# DS2502_Programmer_V1_0.net
KiCad netlist of a schematic drawn in EAGLE
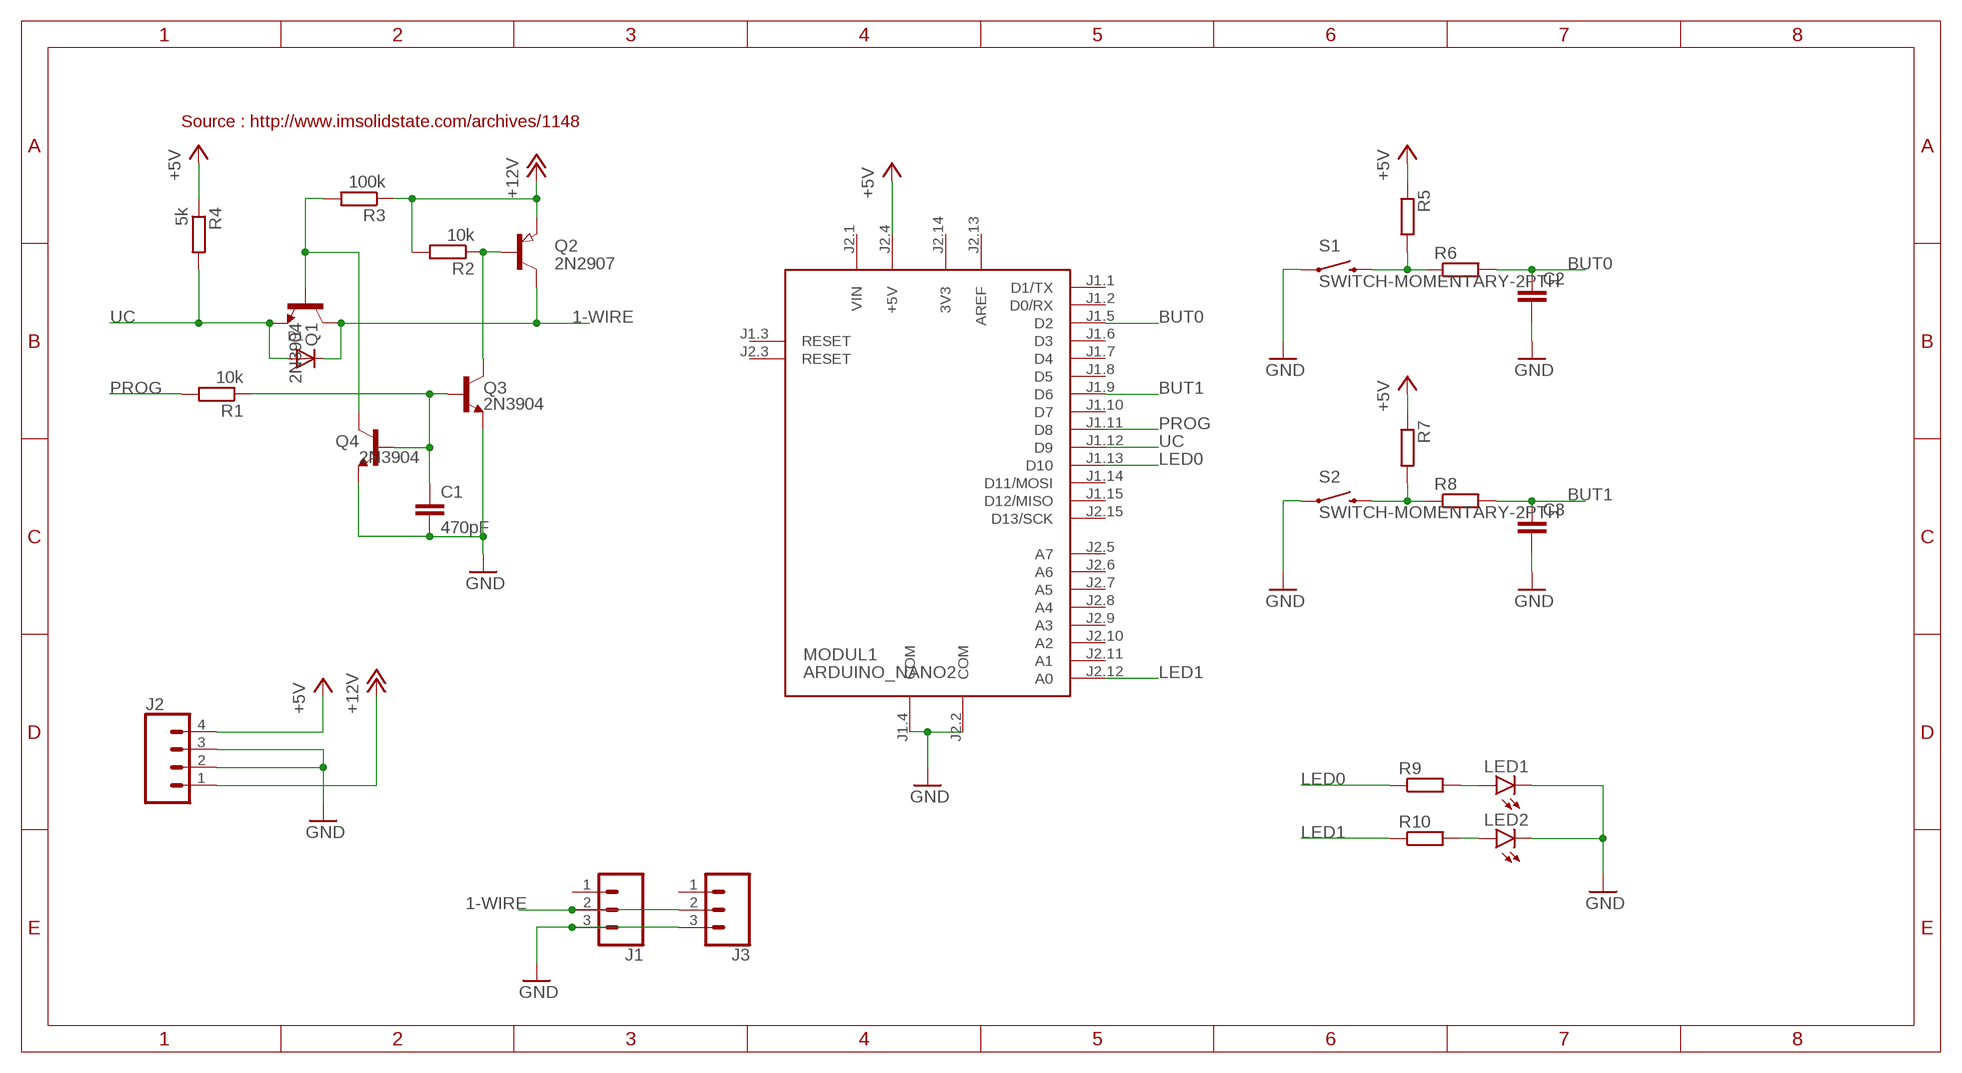
[diagram p0: schematic, sheet 1]

(export (version "E")
  (design (tool "Eeschema 10.0.6"))
  (components
    (comp (ref "C1")
      (value "470pF")
      (footprint "eagle-import:C0603")
      (libsource (lib "eagle-import") (part "C-EUC0603"))
    )
    (comp (ref "C2")
      (value "C-EUC0603")
      (footprint "eagle-import:C0603")
      (libsource (lib "eagle-import") (part "C-EUC0603"))
    )
    (comp (ref "C3")
      (value "C-EUC0603")
      (footprint "eagle-import:C0603")
      (libsource (lib "eagle-import") (part "C-EUC0603"))
    )
    (comp (ref "D1")
      (value "DIODESOD-523")
      (footprint "eagle-import:SOD-523")
      (libsource (lib "eagle-import") (part "DIODESOD-523"))
    )
    (comp (ref "J1")
      (value "CONN_03")
      (footprint "eagle-import:1X03")
      (libsource (lib "eagle-import") (part "CONN_03"))
    )
    (comp (ref "J2")
      (value "CONN_04")
      (footprint "eagle-import:1X04")
      (libsource (lib "eagle-import") (part "CONN_04"))
    )
    (comp (ref "J3")
      (value "CONN_03")
      (footprint "eagle-import:1X03")
      (libsource (lib "eagle-import") (part "CONN_03"))
    )
    (comp (ref "LED1")
      (value "LEDCHIP-LED0805")
      (footprint "eagle-import:CHIP-LED0805")
      (libsource (lib "eagle-import") (part "LEDCHIP-LED0805"))
    )
    (comp (ref "LED2")
      (value "LEDCHIP-LED0805")
      (footprint "eagle-import:CHIP-LED0805")
      (libsource (lib "eagle-import") (part "LEDCHIP-LED0805"))
    )
    (comp (ref "MODUL1")
      (value "ARDUINO_NANO2")
      (footprint "eagle-import:ARDUINO_NANO2")
      (libsource (lib "eagle-import") (part "ARDUINO_NANO2"))
    )
    (comp (ref "Q1")
      (value "2N3904")
      (footprint "eagle-import:SOT23-3")
      (libsource (lib "eagle-import") (part "TRANS_NPN-MMBTA42"))
    )
    (comp (ref "Q2")
      (value "2N2907")
      (footprint "eagle-import:SOT23")
      (libsource (lib "eagle-import") (part "PNP-TRANSISTOR_SOT23"))
    )
    (comp (ref "Q3")
      (value "2N3904")
      (footprint "eagle-import:SOT23-3")
      (libsource (lib "eagle-import") (part "TRANS_NPN-MMBTA42"))
    )
    (comp (ref "Q4")
      (value "2N3904")
      (footprint "eagle-import:SOT23-3")
      (libsource (lib "eagle-import") (part "TRANS_NPN-MMBTA42"))
    )
    (comp (ref "R1")
      (value "10k")
      (footprint "eagle-import:R0603")
      (libsource (lib "eagle-import") (part "R-EU_R0603"))
    )
    (comp (ref "R2")
      (value "10k")
      (footprint "eagle-import:R0603")
      (libsource (lib "eagle-import") (part "R-EU_R0603"))
    )
    (comp (ref "R3")
      (value "100k")
      (footprint "eagle-import:R0603")
      (libsource (lib "eagle-import") (part "R-EU_R0603"))
    )
    (comp (ref "R4")
      (value "5k")
      (footprint "eagle-import:R0603")
      (libsource (lib "eagle-import") (part "R-EU_R0603"))
    )
    (comp (ref "R5")
      (value "R-EU_R0603")
      (footprint "eagle-import:R0603")
      (libsource (lib "eagle-import") (part "R-EU_R0603"))
    )
    (comp (ref "R6")
      (value "R-EU_R0603")
      (footprint "eagle-import:R0603")
      (libsource (lib "eagle-import") (part "R-EU_R0603"))
    )
    (comp (ref "R7")
      (value "R-EU_R0603")
      (footprint "eagle-import:R0603")
      (libsource (lib "eagle-import") (part "R-EU_R0603"))
    )
    (comp (ref "R8")
      (value "R-EU_R0603")
      (footprint "eagle-import:R0603")
      (libsource (lib "eagle-import") (part "R-EU_R0603"))
    )
    (comp (ref "R9")
      (value "R-EU_R0603")
      (footprint "eagle-import:R0603")
      (libsource (lib "eagle-import") (part "R-EU_R0603"))
    )
    (comp (ref "R10")
      (value "R-EU_R0603")
      (footprint "eagle-import:R0603")
      (libsource (lib "eagle-import") (part "R-EU_R0603"))
    )
    (comp (ref "S1")
      (value "SWITCH-MOMENTARY-2PTH")
      (footprint "eagle-import:TACTILE-PTH")
      (libsource (lib "eagle-import") (part "SWITCH-MOMENTARY-2PTH"))
    )
    (comp (ref "S2")
      (value "SWITCH-MOMENTARY-2PTH")
      (footprint "eagle-import:TACTILE-PTH")
      (libsource (lib "eagle-import") (part "SWITCH-MOMENTARY-2PTH"))
    )
  )
  (nets
    (net (code "1") (name "+5V") (class "Default")
      (node (ref "J2") (pin "4") (pinfunction "4_4") (pintype "passive"))
      (node (ref "MODUL1") (pin "J2.4") (pinfunction "+5V_J2.4") (pintype "power_in"))
      (node (ref "R4") (pin "1") (pinfunction "1_1") (pintype "passive"))
      (node (ref "R5") (pin "1") (pinfunction "1_1") (pintype "passive"))
      (node (ref "R7") (pin "1") (pinfunction "1_1") (pintype "passive"))
    )
    (net (code "2") (name "+12V") (class "Default")
      (node (ref "J2") (pin "1") (pinfunction "1_1") (pintype "passive"))
      (node (ref "Q2") (pin "2") (pinfunction "E_2") (pintype "passive"))
      (node (ref "R2") (pin "2") (pinfunction "2_2") (pintype "passive"))
      (node (ref "R3") (pin "1") (pinfunction "1_1") (pintype "passive"))
    )
    (net (code "3") (name "/1-WIRE") (class "Default")
      (node (ref "D1") (pin "K") (pinfunction "C_K") (pintype "passive"))
      (node (ref "J1") (pin "2") (pinfunction "2_2") (pintype "passive"))
      (node (ref "J3") (pin "2") (pinfunction "2_2") (pintype "passive"))
      (node (ref "Q1") (pin "3") (pinfunction "C_3") (pintype "passive"))
      (node (ref "Q2") (pin "3") (pinfunction "C_3") (pintype "passive"))
    )
    (net (code "4") (name "/3V3") (class "Default")
      (node (ref "MODUL1") (pin "J2.14") (pinfunction "3V3_J2.14") (pintype "power_in"))
    )
    (net (code "5") (name "/AREF") (class "Default")
      (node (ref "MODUL1") (pin "J2.13") (pinfunction "AREF_J2.13") (pintype "power_in"))
    )
    (net (code "6") (name "/BUT0") (class "Default")
      (node (ref "C2") (pin "1") (pinfunction "1_1") (pintype "passive"))
      (node (ref "MODUL1") (pin "J1.5") (pinfunction "D2_J1.5") (pintype "bidirectional"))
      (node (ref "R6") (pin "2") (pinfunction "2_2") (pintype "passive"))
    )
    (net (code "7") (name "/BUT1") (class "Default")
      (node (ref "C3") (pin "1") (pinfunction "1_1") (pintype "passive"))
      (node (ref "MODUL1") (pin "J1.9") (pinfunction "D6_J1.9") (pintype "bidirectional"))
      (node (ref "R8") (pin "2") (pinfunction "2_2") (pintype "passive"))
    )
    (net (code "8") (name "/LED0") (class "Default")
      (node (ref "MODUL1") (pin "J1.13") (pinfunction "D10_J1.13") (pintype "bidirectional"))
      (node (ref "R9") (pin "1") (pinfunction "1_1") (pintype "passive"))
    )
    (net (code "9") (name "/LED1") (class "Default")
      (node (ref "MODUL1") (pin "J2.12") (pinfunction "A0_J2.12") (pintype "bidirectional"))
      (node (ref "R10") (pin "1") (pinfunction "1_1") (pintype "passive"))
    )
    (net (code "10") (name "/PROG") (class "Default")
      (node (ref "MODUL1") (pin "J1.11") (pinfunction "D8_J1.11") (pintype "bidirectional"))
      (node (ref "R1") (pin "2") (pinfunction "2_2") (pintype "passive"))
    )
    (net (code "11") (name "/UC") (class "Default")
      (node (ref "D1") (pin "A") (pinfunction "A_A") (pintype "passive"))
      (node (ref "MODUL1") (pin "J1.12") (pinfunction "D9_J1.12") (pintype "bidirectional"))
      (node (ref "Q1") (pin "2") (pinfunction "E_2") (pintype "passive"))
      (node (ref "R4") (pin "2") (pinfunction "2_2") (pintype "passive"))
    )
    (net (code "12") (name "/VIN") (class "Default")
      (node (ref "MODUL1") (pin "J2.1") (pinfunction "VIN_J2.1") (pintype "power_in"))
    )
    (net (code "13") (name "GND") (class "Default")
      (node (ref "C1") (pin "2") (pinfunction "2_2") (pintype "passive"))
      (node (ref "C2") (pin "2") (pinfunction "2_2") (pintype "passive"))
      (node (ref "C3") (pin "2") (pinfunction "2_2") (pintype "passive"))
      (node (ref "J1") (pin "3") (pinfunction "3_3") (pintype "passive"))
      (node (ref "J2") (pin "2") (pinfunction "2_2") (pintype "passive"))
      (node (ref "J2") (pin "3") (pinfunction "3_3") (pintype "passive"))
      (node (ref "J3") (pin "3") (pinfunction "3_3") (pintype "passive"))
      (node (ref "LED1") (pin "C") (pinfunction "C_C") (pintype "passive"))
      (node (ref "LED2") (pin "C") (pinfunction "C_C") (pintype "passive"))
      (node (ref "MODUL1") (pin "J1.4") (pinfunction "COM_J1.4") (pintype "power_in"))
      (node (ref "MODUL1") (pin "J2.2") (pinfunction "COM_J2.2") (pintype "power_in"))
      (node (ref "Q3") (pin "2") (pinfunction "E_2") (pintype "passive"))
      (node (ref "Q4") (pin "2") (pinfunction "E_2") (pintype "passive"))
      (node (ref "S1") (pin "1") (pinfunction "1_1") (pintype "passive"))
      (node (ref "S2") (pin "1") (pinfunction "1_1") (pintype "passive"))
    )
    (net (code "14") (name "Net-(LED1-PadA)") (class "Default")
      (node (ref "LED1") (pin "A") (pinfunction "A_A") (pintype "passive"))
      (node (ref "R9") (pin "2") (pinfunction "2_2") (pintype "passive"))
    )
    (net (code "15") (name "Net-(LED2-PadA)") (class "Default")
      (node (ref "LED2") (pin "A") (pinfunction "A_A") (pintype "passive"))
      (node (ref "R10") (pin "2") (pinfunction "2_2") (pintype "passive"))
    )
    (net (code "16") (name "Net-(Q1-B)") (class "Default")
      (node (ref "Q1") (pin "1") (pinfunction "B_1") (pintype "passive"))
      (node (ref "Q4") (pin "3") (pinfunction "C_3") (pintype "passive"))
      (node (ref "R3") (pin "2") (pinfunction "2_2") (pintype "passive"))
    )
    (net (code "17") (name "Net-(Q2-B)") (class "Default")
      (node (ref "Q2") (pin "1") (pinfunction "B_1") (pintype "passive"))
      (node (ref "Q3") (pin "3") (pinfunction "C_3") (pintype "passive"))
      (node (ref "R2") (pin "1") (pinfunction "1_1") (pintype "passive"))
    )
    (net (code "18") (name "Net-(Q3-B)") (class "Default")
      (node (ref "C1") (pin "1") (pinfunction "1_1") (pintype "passive"))
      (node (ref "Q3") (pin "1") (pinfunction "B_1") (pintype "passive"))
      (node (ref "Q4") (pin "1") (pinfunction "B_1") (pintype "passive"))
      (node (ref "R1") (pin "1") (pinfunction "1_1") (pintype "passive"))
    )
    (net (code "19") (name "Net-(S1-2)") (class "Default")
      (node (ref "R5") (pin "2") (pinfunction "2_2") (pintype "passive"))
      (node (ref "R6") (pin "1") (pinfunction "1_1") (pintype "passive"))
      (node (ref "S1") (pin "3") (pinfunction "2_3") (pintype "passive"))
    )
    (net (code "20") (name "Net-(S2-2)") (class "Default")
      (node (ref "R7") (pin "2") (pinfunction "2_2") (pintype "passive"))
      (node (ref "R8") (pin "1") (pinfunction "1_1") (pintype "passive"))
      (node (ref "S2") (pin "3") (pinfunction "2_3") (pintype "passive"))
    )
    (net (code "21") (name "unconnected-(J1-Pad1)") (class "Default")
      (node (ref "J1") (pin "1") (pinfunction "1_1") (pintype "passive"))
    )
    (net (code "22") (name "unconnected-(J3-Pad1)") (class "Default")
      (node (ref "J3") (pin "1") (pinfunction "1_1") (pintype "passive"))
    )
    (net (code "23") (name "unconnected-(MODUL1-A1-PadJ2.11)") (class "Default")
      (node (ref "MODUL1") (pin "J2.11") (pinfunction "A1_J2.11") (pintype "bidirectional"))
    )
    (net (code "24") (name "unconnected-(MODUL1-A2-PadJ2.10)") (class "Default")
      (node (ref "MODUL1") (pin "J2.10") (pinfunction "A2_J2.10") (pintype "bidirectional"))
    )
    (net (code "25") (name "unconnected-(MODUL1-A3-PadJ2.9)") (class "Default")
      (node (ref "MODUL1") (pin "J2.9") (pinfunction "A3_J2.9") (pintype "bidirectional"))
    )
    (net (code "26") (name "unconnected-(MODUL1-A4-PadJ2.8)") (class "Default")
      (node (ref "MODUL1") (pin "J2.8") (pinfunction "A4_J2.8") (pintype "bidirectional"))
    )
    (net (code "27") (name "unconnected-(MODUL1-A5-PadJ2.7)") (class "Default")
      (node (ref "MODUL1") (pin "J2.7") (pinfunction "A5_J2.7") (pintype "bidirectional"))
    )
    (net (code "28") (name "unconnected-(MODUL1-A6-PadJ2.6)") (class "Default")
      (node (ref "MODUL1") (pin "J2.6") (pinfunction "A6_J2.6") (pintype "bidirectional"))
    )
    (net (code "29") (name "unconnected-(MODUL1-A7-PadJ2.5)") (class "Default")
      (node (ref "MODUL1") (pin "J2.5") (pinfunction "A7_J2.5") (pintype "bidirectional"))
    )
    (net (code "30") (name "unconnected-(MODUL1-D0{slash}RX-PadJ1.2)") (class "Default")
      (node (ref "MODUL1") (pin "J1.2") (pinfunction "D0/RX_J1.2") (pintype "bidirectional"))
    )
    (net (code "31") (name "unconnected-(MODUL1-D1{slash}TX-PadJ1.1)") (class "Default")
      (node (ref "MODUL1") (pin "J1.1") (pinfunction "D1/TX_J1.1") (pintype "bidirectional"))
    )
    (net (code "32") (name "unconnected-(MODUL1-D3-PadJ1.6)") (class "Default")
      (node (ref "MODUL1") (pin "J1.6") (pinfunction "D3_J1.6") (pintype "bidirectional"))
    )
    (net (code "33") (name "unconnected-(MODUL1-D4-PadJ1.7)") (class "Default")
      (node (ref "MODUL1") (pin "J1.7") (pinfunction "D4_J1.7") (pintype "bidirectional"))
    )
    (net (code "34") (name "unconnected-(MODUL1-D5-PadJ1.8)") (class "Default")
      (node (ref "MODUL1") (pin "J1.8") (pinfunction "D5_J1.8") (pintype "bidirectional"))
    )
    (net (code "35") (name "unconnected-(MODUL1-D7-PadJ1.10)") (class "Default")
      (node (ref "MODUL1") (pin "J1.10") (pinfunction "D7_J1.10") (pintype "bidirectional"))
    )
    (net (code "36") (name "unconnected-(MODUL1-D11{slash}MOSI-PadJ1.14)") (class "Default")
      (node (ref "MODUL1") (pin "J1.14") (pinfunction "D11/MOSI_J1.14") (pintype "bidirectional"))
    )
    (net (code "37") (name "unconnected-(MODUL1-D12{slash}MISO-PadJ1.15)") (class "Default")
      (node (ref "MODUL1") (pin "J1.15") (pinfunction "D12/MISO_J1.15") (pintype "bidirectional"))
    )
    (net (code "38") (name "unconnected-(MODUL1-D13{slash}SCK-PadJ2.15)") (class "Default")
      (node (ref "MODUL1") (pin "J2.15") (pinfunction "D13/SCK_J2.15") (pintype "bidirectional"))
    )
    (net (code "39") (name "unconnected-(MODUL1-RESET-PadJ1.3)") (class "Default")
      (node (ref "MODUL1") (pin "J1.3") (pinfunction "RESET_J1.3") (pintype "bidirectional"))
    )
    (net (code "40") (name "unconnected-(MODUL1-RESET-PadJ2.3)") (class "Default")
      (node (ref "MODUL1") (pin "J2.3") (pinfunction "RESET_J2.3") (pintype "bidirectional"))
    )
  )
)
